# PowerSupply.net
KiCad netlist of a schematic drawn in Altium Designer
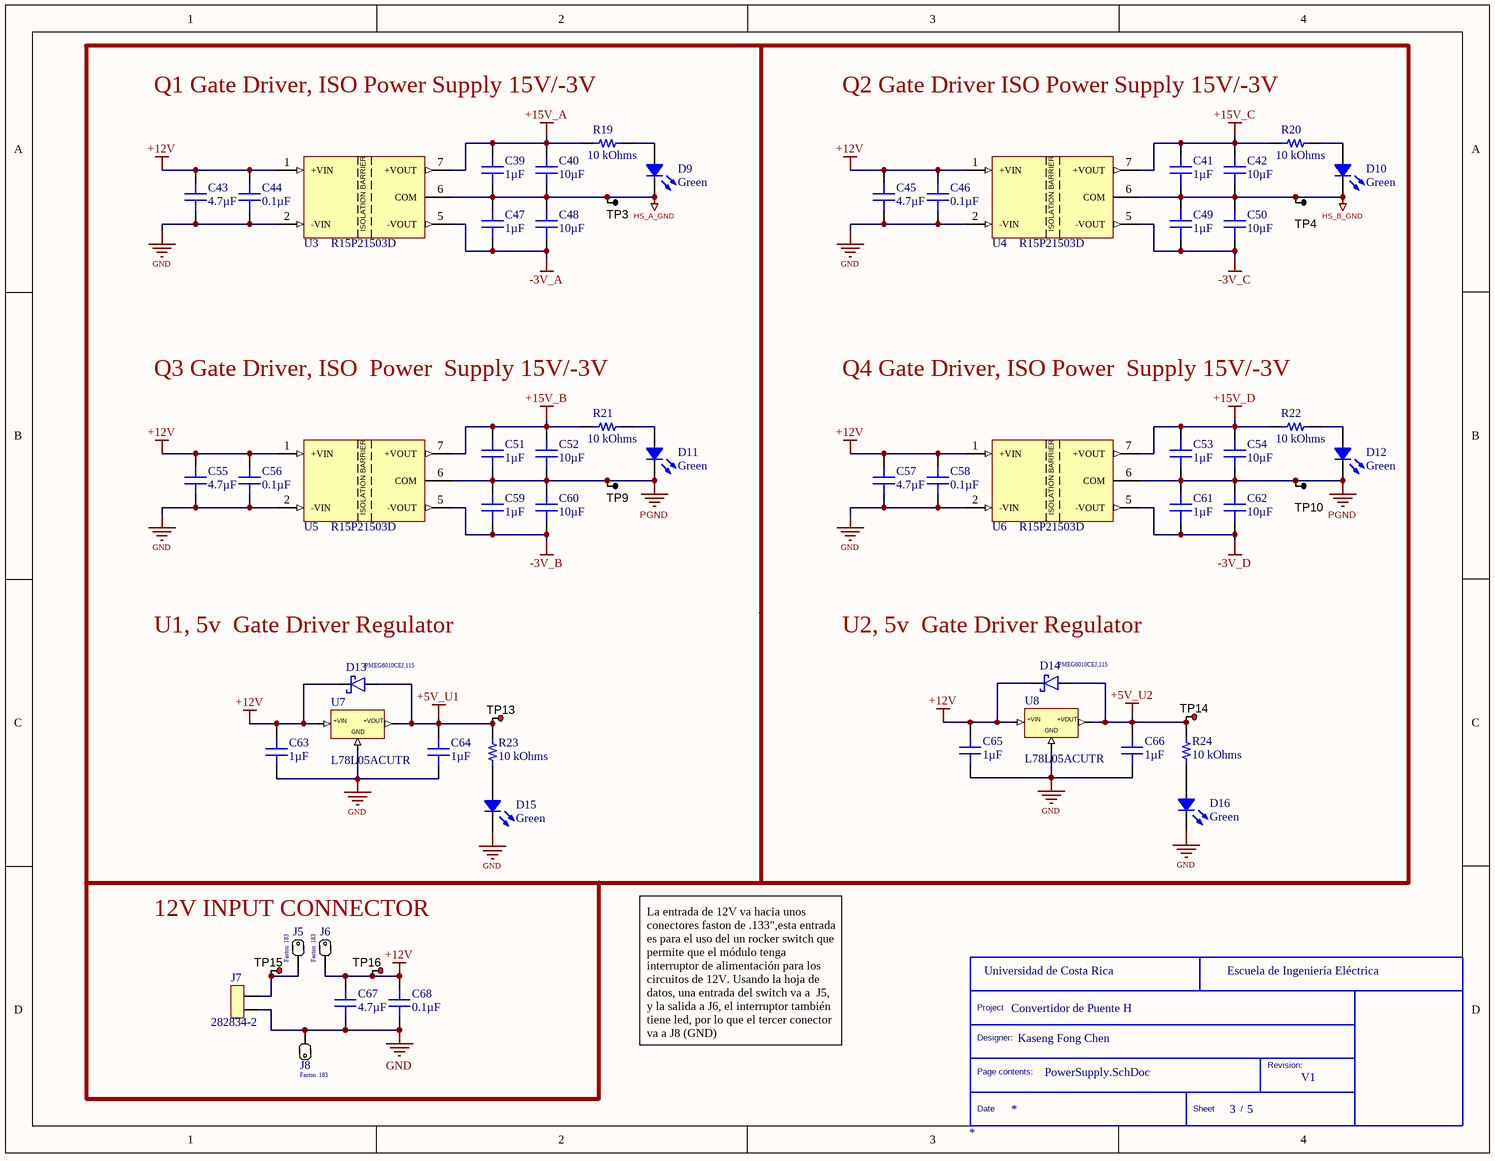
[diagram p0: PowerSupply.SchDoc]

(export (version "E")
  (design (tool "Eeschema 10.0.6"))
  (components
    (comp (ref "C39")
      (value "1µF")
      (footprint "CAP 0603_1608")
      (description "CAP CER 1UF 50V X7R 0603")
      (fields (field (name "PART NUMBER") "UMK107AB7105KA-T") (field (name "MANUFACTURER") "Taiyo Yuden"))
      (libsource (lib "Celestial Altium Library - altium_library") (part "Capacitor"))
    )
    (comp (ref "C40")
      (value "10µF")
      (footprint "CAP 1206_3216 - 1.8MM")
      (description "CAP CER 10UF 25V X7R 1206")
      (fields (field (name "PART NUMBER") "TMK316AB7106KL-T") (field (name "MANUFACTURER") "Taiyo Yuden"))
      (libsource (lib "Celestial Altium Library - altium_library") (part "Capacitor"))
    )
    (comp (ref "C41")
      (value "1µF")
      (footprint "CAP 0603_1608")
      (description "CAP CER 1UF 50V X7R 0603")
      (fields (field (name "PART NUMBER") "UMK107AB7105KA-T") (field (name "MANUFACTURER") "Taiyo Yuden"))
      (libsource (lib "Celestial Altium Library - altium_library") (part "Capacitor"))
    )
    (comp (ref "C42")
      (value "10µF")
      (footprint "CAP 1206_3216 - 1.8MM")
      (description "CAP CER 10UF 25V X7R 1206")
      (fields (field (name "PART NUMBER") "TMK316AB7106KL-T") (field (name "MANUFACTURER") "Taiyo Yuden"))
      (libsource (lib "Celestial Altium Library - altium_library") (part "Capacitor"))
    )
    (comp (ref "C43")
      (value "4.7µF")
      (footprint "CAP 1206_3216 - 1.8MM")
      (description "CAP CER 4.7UF 50V X7R 1206")
      (fields (field (name "PART NUMBER") "UMK316AB7475KL-T") (field (name "MANUFACTURER") "Taiyo Yuden"))
      (libsource (lib "Celestial Altium Library - altium_library") (part "Capacitor"))
    )
    (comp (ref "C44")
      (value "0.1µF")
      (footprint "CAP 0603_1608")
      (description "CAP CER 0.1UF 50V X7R 0603")
      (fields (field (name "PART NUMBER") "C0603C104M5RACTU") (field (name "MANUFACTURER") "KEMET"))
      (libsource (lib "Celestial Altium Library - altium_library") (part "Capacitor"))
    )
    (comp (ref "C45")
      (value "4.7µF")
      (footprint "CAP 1206_3216 - 1.8MM")
      (description "CAP CER 4.7UF 50V X7R 1206")
      (fields (field (name "PART NUMBER") "UMK316AB7475KL-T") (field (name "MANUFACTURER") "Taiyo Yuden"))
      (libsource (lib "Celestial Altium Library - altium_library") (part "Capacitor"))
    )
    (comp (ref "C46")
      (value "0.1µF")
      (footprint "CAP 0603_1608")
      (description "CAP CER 0.1UF 50V X7R 0603")
      (fields (field (name "PART NUMBER") "C0603C104M5RACTU") (field (name "MANUFACTURER") "KEMET"))
      (libsource (lib "Celestial Altium Library - altium_library") (part "Capacitor"))
    )
    (comp (ref "C47")
      (value "1µF")
      (footprint "CAP 0603_1608")
      (description "CAP CER 1UF 50V X7R 0603")
      (fields (field (name "PART NUMBER") "UMK107AB7105KA-T") (field (name "MANUFACTURER") "Taiyo Yuden"))
      (libsource (lib "Celestial Altium Library - altium_library") (part "Capacitor"))
    )
    (comp (ref "C48")
      (value "10µF")
      (footprint "CAP 1206_3216 - 1.8MM")
      (description "CAP CER 10UF 25V X7R 1206")
      (fields (field (name "PART NUMBER") "TMK316AB7106KL-T") (field (name "MANUFACTURER") "Taiyo Yuden"))
      (libsource (lib "Celestial Altium Library - altium_library") (part "Capacitor"))
    )
    (comp (ref "C49")
      (value "1µF")
      (footprint "CAP 0603_1608")
      (description "CAP CER 1UF 50V X7R 0603")
      (fields (field (name "PART NUMBER") "UMK107AB7105KA-T") (field (name "MANUFACTURER") "Taiyo Yuden"))
      (libsource (lib "Celestial Altium Library - altium_library") (part "Capacitor"))
    )
    (comp (ref "C50")
      (value "10µF")
      (footprint "CAP 1206_3216 - 1.8MM")
      (description "CAP CER 10UF 25V X7R 1206")
      (fields (field (name "PART NUMBER") "TMK316AB7106KL-T") (field (name "MANUFACTURER") "Taiyo Yuden"))
      (libsource (lib "Celestial Altium Library - altium_library") (part "Capacitor"))
    )
    (comp (ref "C51")
      (value "1µF")
      (footprint "CAP 0603_1608")
      (description "CAP CER 1UF 50V X7R 0603")
      (fields (field (name "PART NUMBER") "UMK107AB7105KA-T") (field (name "MANUFACTURER") "Taiyo Yuden"))
      (libsource (lib "Celestial Altium Library - altium_library") (part "Capacitor"))
    )
    (comp (ref "C52")
      (value "10µF")
      (footprint "CAP 1206_3216 - 1.8MM")
      (description "CAP CER 10UF 25V X7R 1206")
      (fields (field (name "PART NUMBER") "TMK316AB7106KL-T") (field (name "MANUFACTURER") "Taiyo Yuden"))
      (libsource (lib "Celestial Altium Library - altium_library") (part "Capacitor"))
    )
    (comp (ref "C53")
      (value "1µF")
      (footprint "CAP 0603_1608")
      (description "CAP CER 1UF 50V X7R 0603")
      (fields (field (name "PART NUMBER") "UMK107AB7105KA-T") (field (name "MANUFACTURER") "Taiyo Yuden"))
      (libsource (lib "Celestial Altium Library - altium_library") (part "Capacitor"))
    )
    (comp (ref "C54")
      (value "10µF")
      (footprint "CAP 1206_3216 - 1.8MM")
      (description "CAP CER 10UF 25V X7R 1206")
      (fields (field (name "PART NUMBER") "TMK316AB7106KL-T") (field (name "MANUFACTURER") "Taiyo Yuden"))
      (libsource (lib "Celestial Altium Library - altium_library") (part "Capacitor"))
    )
    (comp (ref "C55")
      (value "4.7µF")
      (footprint "CAP 1206_3216 - 1.8MM")
      (description "CAP CER 4.7UF 50V X7R 1206")
      (fields (field (name "PART NUMBER") "UMK316AB7475KL-T") (field (name "MANUFACTURER") "Taiyo Yuden"))
      (libsource (lib "Celestial Altium Library - altium_library") (part "Capacitor"))
    )
    (comp (ref "C56")
      (value "0.1µF")
      (footprint "CAP 0603_1608")
      (description "CAP CER 0.1UF 50V X7R 0603")
      (fields (field (name "PART NUMBER") "C0603C104M5RACTU") (field (name "MANUFACTURER") "KEMET"))
      (libsource (lib "Celestial Altium Library - altium_library") (part "Capacitor"))
    )
    (comp (ref "C57")
      (value "4.7µF")
      (footprint "CAP 1206_3216 - 1.8MM")
      (description "CAP CER 4.7UF 50V X7R 1206")
      (fields (field (name "PART NUMBER") "UMK316AB7475KL-T") (field (name "MANUFACTURER") "Taiyo Yuden"))
      (libsource (lib "Celestial Altium Library - altium_library") (part "Capacitor"))
    )
    (comp (ref "C58")
      (value "0.1µF")
      (footprint "CAP 0603_1608")
      (description "CAP CER 0.1UF 50V X7R 0603")
      (fields (field (name "PART NUMBER") "C0603C104M5RACTU") (field (name "MANUFACTURER") "KEMET"))
      (libsource (lib "Celestial Altium Library - altium_library") (part "Capacitor"))
    )
    (comp (ref "C59")
      (value "1µF")
      (footprint "CAP 0603_1608")
      (description "CAP CER 1UF 50V X7R 0603")
      (fields (field (name "PART NUMBER") "UMK107AB7105KA-T") (field (name "MANUFACTURER") "Taiyo Yuden"))
      (libsource (lib "Celestial Altium Library - altium_library") (part "Capacitor"))
    )
    (comp (ref "C60")
      (value "10µF")
      (footprint "CAP 1206_3216 - 1.8MM")
      (description "CAP CER 10UF 25V X7R 1206")
      (fields (field (name "PART NUMBER") "TMK316AB7106KL-T") (field (name "MANUFACTURER") "Taiyo Yuden"))
      (libsource (lib "Celestial Altium Library - altium_library") (part "Capacitor"))
    )
    (comp (ref "C61")
      (value "1µF")
      (footprint "CAP 0603_1608")
      (description "CAP CER 1UF 50V X7R 0603")
      (fields (field (name "PART NUMBER") "UMK107AB7105KA-T") (field (name "MANUFACTURER") "Taiyo Yuden"))
      (libsource (lib "Celestial Altium Library - altium_library") (part "Capacitor"))
    )
    (comp (ref "C62")
      (value "10µF")
      (footprint "CAP 1206_3216 - 1.8MM")
      (description "CAP CER 10UF 25V X7R 1206")
      (fields (field (name "PART NUMBER") "TMK316AB7106KL-T") (field (name "MANUFACTURER") "Taiyo Yuden"))
      (libsource (lib "Celestial Altium Library - altium_library") (part "Capacitor"))
    )
    (comp (ref "C63")
      (value "1µF")
      (footprint "CAP 0603_1608")
      (description "CAP CER 1UF 25V X7R 0603")
      (fields (field (name "PART NUMBER") "TMK107B7105KA-T") (field (name "MANUFACTURER") "Taiyo Yuden"))
      (libsource (lib "Celestial Altium Library - altium_library") (part "Capacitor"))
    )
    (comp (ref "C64")
      (value "1µF")
      (footprint "CAP 0603_1608")
      (description "CAP CER 1UF 16V X7R 0603")
      (fields (field (name "PART NUMBER") "CC0603KRX7R7BB105") (field (name "MANUFACTURER") "Yageo"))
      (libsource (lib "Celestial Altium Library - altium_library") (part "Capacitor"))
    )
    (comp (ref "C65")
      (value "1µF")
      (footprint "CAP 0603_1608")
      (description "CAP CER 1UF 25V X7R 0603")
      (fields (field (name "PART NUMBER") "TMK107B7105KA-T") (field (name "MANUFACTURER") "Taiyo Yuden"))
      (libsource (lib "Celestial Altium Library - altium_library") (part "Capacitor"))
    )
    (comp (ref "C66")
      (value "1µF")
      (footprint "CAP 0603_1608")
      (description "CAP CER 1UF 16V X7R 0603")
      (fields (field (name "PART NUMBER") "CC0603KRX7R7BB105") (field (name "MANUFACTURER") "Yageo"))
      (libsource (lib "Celestial Altium Library - altium_library") (part "Capacitor"))
    )
    (comp (ref "C67")
      (value "4.7µF")
      (footprint "CAP 1206_3216 - 1.8MM")
      (description "CAP CER 4.7UF 50V X7R 1206")
      (fields (field (name "PART NUMBER") "UMK316AB7475KL-T") (field (name "MANUFACTURER") "Taiyo Yuden"))
      (libsource (lib "Celestial Altium Library - altium_library") (part "Capacitor"))
    )
    (comp (ref "C68")
      (value "0.1µF")
      (footprint "CAP 0603_1608")
      (description "CAP CER 0.1UF 50V X7R 0603")
      (fields (field (name "PART NUMBER") "C0603C104M5RACTU") (field (name "MANUFACTURER") "KEMET"))
      (libsource (lib "Celestial Altium Library - altium_library") (part "Capacitor"))
    )
    (comp (ref "D9")
      (value "Green")
      (footprint "LED 0603_1608 GREEN")
      (description "LED GREEN CLEAR 0603 SMD")
      (fields (field (name "PART NUMBER") "150060GS75000") (field (name "MANUFACTURER") "Würth Elektronik"))
      (libsource (lib "Celestial Altium Library - altium_library") (part "LED"))
    )
    (comp (ref "D10")
      (value "Green")
      (footprint "LED 0603_1608 GREEN")
      (description "LED GREEN CLEAR 0603 SMD")
      (fields (field (name "PART NUMBER") "150060GS75000") (field (name "MANUFACTURER") "Würth Elektronik"))
      (libsource (lib "Celestial Altium Library - altium_library") (part "LED"))
    )
    (comp (ref "D11")
      (value "Green")
      (footprint "LED 0603_1608 GREEN")
      (description "LED GREEN CLEAR 0603 SMD")
      (fields (field (name "PART NUMBER") "150060GS75000") (field (name "MANUFACTURER") "Würth Elektronik"))
      (libsource (lib "Celestial Altium Library - altium_library") (part "LED"))
    )
    (comp (ref "D12")
      (value "Green")
      (footprint "LED 0603_1608 GREEN")
      (description "LED GREEN CLEAR 0603 SMD")
      (fields (field (name "PART NUMBER") "150060GS75000") (field (name "MANUFACTURER") "Würth Elektronik"))
      (libsource (lib "Celestial Altium Library - altium_library") (part "LED"))
    )
    (comp (ref "D13")
      (value "PMEG6010CEJ,115")
      (footprint "SOD-323F")
      (description "PMEG6010CEH; PMEG6010CEJ - 1 A very low VF MEGA Schottky barrier rectifiers")
      (fields (field (name "MANUFACTURER") "Nexperia"))
      (libsource (lib "KasengLIb") (part "PMEG6010CEJ,115"))
    )
    (comp (ref "D14")
      (value "PMEG6010CEJ,115")
      (footprint "SOD-323F")
      (description "PMEG6010CEH; PMEG6010CEJ - 1 A very low VF MEGA Schottky barrier rectifiers")
      (fields (field (name "MANUFACTURER") "Nexperia"))
      (libsource (lib "KasengLIb") (part "PMEG6010CEJ,115"))
    )
    (comp (ref "D15")
      (value "Green")
      (footprint "LED 0603_1608 GREEN")
      (description "LED GREEN CLEAR 0603 SMD")
      (fields (field (name "PART NUMBER") "150060GS75000") (field (name "MANUFACTURER") "Würth Elektronik"))
      (libsource (lib "Celestial Altium Library - altium_library") (part "LED"))
    )
    (comp (ref "D16")
      (value "Green")
      (footprint "LED 0603_1608 GREEN")
      (description "LED GREEN CLEAR 0603 SMD")
      (fields (field (name "PART NUMBER") "150060GS75000") (field (name "MANUFACTURER") "Würth Elektronik"))
      (libsource (lib "Celestial Altium Library - altium_library") (part "LED"))
    )
    (comp (ref "J5")
      (value "Faston .183")
      (footprint "TE_1217133-1")
      (description "FASTON 187 PCB TAB TPBR")
      (fields (field (name "MP") "1217133-1") (field (name "MF") "TE Connectivity"))
      (libsource (lib "1217133-1") (part "1217133-1"))
    )
    (comp (ref "J6")
      (value "Faston .183")
      (footprint "TE_1217133-1")
      (description "FASTON 187 PCB TAB TPBR")
      (fields (field (name "MP") "1217133-1") (field (name "MF") "TE Connectivity"))
      (libsource (lib "1217133-1") (part "1217133-1"))
    )
    (comp (ref "J7")
      (value "282834-2")
      (footprint "TE 282834-2")
      (description "TE CONNECTIVITY / BUCHANAN - 282834-2 - TERMINAL BLOCK, WIRE TO BRD, 2POS, 16AWG")
      (fields (field (name "MANUFACTURER") "TE Connectivity") (field (name "VOLTAGE") "150V"))
      (libsource (lib "kasengLib") (part "282834-2"))
    )
    (comp (ref "J8")
      (value "Faston .183")
      (footprint "TE_1217133-1")
      (description "FASTON 187 PCB TAB TPBR")
      (fields (field (name "MP") "1217133-1") (field (name "MF") "TE Connectivity"))
      (libsource (lib "1217133-1") (part "1217133-1"))
    )
    (comp (ref "R19")
      (value "10 kOhms")
      (footprint "RES 0603_1608")
      (description "RES SMD 10K OHM 1% 1/10W 0603")
      (fields (field (name "PART NUMBER") "RC0603FR-0710KL") (field (name "MANUFACTURER") "Yageo"))
      (libsource (lib "Celestial Altium Library - altium_library") (part "Resistor"))
    )
    (comp (ref "R20")
      (value "10 kOhms")
      (footprint "RES 0603_1608")
      (description "RES SMD 10K OHM 1% 1/10W 0603")
      (fields (field (name "PART NUMBER") "RC0603FR-0710KL") (field (name "MANUFACTURER") "Yageo"))
      (libsource (lib "Celestial Altium Library - altium_library") (part "Resistor"))
    )
    (comp (ref "R21")
      (value "10 kOhms")
      (footprint "RES 0603_1608")
      (description "RES SMD 10K OHM 1% 1/10W 0603")
      (fields (field (name "PART NUMBER") "RC0603FR-0710KL") (field (name "MANUFACTURER") "Yageo"))
      (libsource (lib "Celestial Altium Library - altium_library") (part "Resistor"))
    )
    (comp (ref "R22")
      (value "10 kOhms")
      (footprint "RES 0603_1608")
      (description "RES SMD 10K OHM 1% 1/10W 0603")
      (fields (field (name "PART NUMBER") "RC0603FR-0710KL") (field (name "MANUFACTURER") "Yageo"))
      (libsource (lib "Celestial Altium Library - altium_library") (part "Resistor"))
    )
    (comp (ref "R23")
      (value "10 kOhms")
      (footprint "RES 0603_1608")
      (description "RES SMD 10K OHM 1% 1/10W 0603")
      (fields (field (name "PART NUMBER") "RC0603FR-0710KL") (field (name "MANUFACTURER") "Yageo"))
      (libsource (lib "Celestial Altium Library - altium_library") (part "Resistor"))
    )
    (comp (ref "R24")
      (value "10 kOhms")
      (footprint "RES 0603_1608")
      (description "RES SMD 10K OHM 1% 1/10W 0603")
      (fields (field (name "PART NUMBER") "RC0603FR-0710KL") (field (name "MANUFACTURER") "Yageo"))
      (libsource (lib "Celestial Altium Library - altium_library") (part "Resistor"))
    )
    (comp (ref "TP3")
      (value "5011")
      (footprint "Keystone5011")
      (description "Test Point, Multipurpose, Black, TH")
      (fields (field (name "MANUFACTURER") "Keystone") (field (name "PUBLISHER") "Texas Instruments"))
      (libsource (lib "kasengLib") (part "5011"))
    )
    (comp (ref "TP4")
      (value "5011")
      (footprint "Keystone5011")
      (description "Test Point, Multipurpose, Black, TH")
      (fields (field (name "MANUFACTURER") "Keystone") (field (name "PUBLISHER") "Texas Instruments"))
      (libsource (lib "kasengLib") (part "5011"))
    )
    (comp (ref "TP9")
      (value "5011")
      (footprint "Keystone5011")
      (description "Test Point, Multipurpose, Black, TH")
      (fields (field (name "MANUFACTURER") "Keystone") (field (name "PUBLISHER") "Texas Instruments"))
      (libsource (lib "kasengLib") (part "5011"))
    )
    (comp (ref "TP10")
      (value "5011")
      (footprint "Keystone5011")
      (description "Test Point, Multipurpose, Black, TH")
      (fields (field (name "MANUFACTURER") "Keystone") (field (name "PUBLISHER") "Texas Instruments"))
      (libsource (lib "kasengLib") (part "5011"))
    )
    (comp (ref "TP13")
      (value "5010")
      (footprint "Keystone5010")
      (description "Test Point, Multipurpose, Red, TH")
      (fields (field (name "MANUFACTURER") "Keystone") (field (name "PUBLISHER") "Texas Instruments"))
      (libsource (lib "kasengLib") (part "5010"))
    )
    (comp (ref "TP14")
      (value "5010")
      (footprint "Keystone5010")
      (description "Test Point, Multipurpose, Red, TH")
      (fields (field (name "MANUFACTURER") "Keystone") (field (name "PUBLISHER") "Texas Instruments"))
      (libsource (lib "kasengLib") (part "5010"))
    )
    (comp (ref "TP15")
      (value "5010")
      (footprint "Keystone5010")
      (description "Test Point, Multipurpose, Red, TH")
      (fields (field (name "MANUFACTURER") "Keystone") (field (name "PUBLISHER") "Texas Instruments"))
      (libsource (lib "kasengLib") (part "5010"))
    )
    (comp (ref "TP16")
      (value "5010")
      (footprint "Keystone5010")
      (description "Test Point, Multipurpose, Red, TH")
      (fields (field (name "MANUFACTURER") "Keystone") (field (name "PUBLISHER") "Texas Instruments"))
      (libsource (lib "kasengLib") (part "5010"))
    )
    (comp (ref "U3")
      (value "R15P21503D")
      (footprint "CONV_R15P21503D")
      (description "2W DC/DC-Converter 'ECONOLINE' SIP7 6.4kV unreg; V. In: 15; V. Out: +15/-03; mA. Out: +93/-185")
      (fields (field (name "MANUFACTURER") "Recom"))
      (libsource (lib "KasengLIb") (part "R15P21503D"))
    )
    (comp (ref "U4")
      (value "R15P21503D")
      (footprint "CONV_R15P21503D")
      (description "2W DC/DC-Converter 'ECONOLINE' SIP7 6.4kV unreg; V. In: 15; V. Out: +15/-03; mA. Out: +93/-185")
      (fields (field (name "MANUFACTURER") "Recom"))
      (libsource (lib "KasengLIb") (part "R15P21503D"))
    )
    (comp (ref "U5")
      (value "R15P21503D")
      (footprint "CONV_R15P21503D")
      (description "2W DC/DC-Converter 'ECONOLINE' SIP7 6.4kV unreg; V. In: 15; V. Out: +15/-03; mA. Out: +93/-185")
      (fields (field (name "MANUFACTURER") "Recom"))
      (libsource (lib "KasengLIb") (part "R15P21503D"))
    )
    (comp (ref "U6")
      (value "R15P21503D")
      (footprint "CONV_R15P21503D")
      (description "2W DC/DC-Converter 'ECONOLINE' SIP7 6.4kV unreg; V. In: 15; V. Out: +15/-03; mA. Out: +93/-185")
      (fields (field (name "MANUFACTURER") "Recom"))
      (libsource (lib "KasengLIb") (part "R15P21503D"))
    )
    (comp (ref "U7")
      (value "L78L05ACUTR")
      (footprint "VREG_L78L12ABUTR")
      (description "Voltage regulator; linear, fixed; 5V; 0.1A; SOT89; SMD; 0÷125°C")
      (fields (field (name "MANUFACTURER") "STMicroelectronics"))
      (libsource (lib "KasengLIb") (part "L78L05ACUTR"))
    )
    (comp (ref "U8")
      (value "L78L05ACUTR")
      (footprint "VREG_L78L12ABUTR")
      (description "Voltage regulator; linear, fixed; 5V; 0.1A; SOT89; SMD; 0÷125°C")
      (fields (field (name "MANUFACTURER") "STMicroelectronics"))
      (libsource (lib "KasengLIb") (part "L78L05ACUTR"))
    )
  )
  (nets
    (net (code "1") (name "+5V_U1") (class "Default")
      (node (ref "C64") (pin "2") (pinfunction "2_2") (pintype "passive"))
      (node (ref "D13") (pin "2") (pinfunction "2_2") (pintype "passive"))
      (node (ref "R23") (pin "1") (pinfunction "1_1") (pintype "passive"))
      (node (ref "TP13") (pin "1") (pinfunction "1_1") (pintype "passive"))
      (node (ref "U7") (pin "1") (pinfunction "OUT_1") (pintype "output"))
    )
    (net (code "2") (name "+5V_U2") (class "Default")
      (node (ref "C66") (pin "2") (pinfunction "2_2") (pintype "passive"))
      (node (ref "D14") (pin "2") (pinfunction "2_2") (pintype "passive"))
      (node (ref "R24") (pin "1") (pinfunction "1_1") (pintype "passive"))
      (node (ref "TP14") (pin "1") (pinfunction "1_1") (pintype "passive"))
      (node (ref "U8") (pin "1") (pinfunction "OUT_1") (pintype "output"))
    )
    (net (code "3") (name "+12V") (class "Default")
      (node (ref "C43") (pin "2") (pinfunction "2_2") (pintype "passive"))
      (node (ref "C44") (pin "2") (pinfunction "2_2") (pintype "passive"))
      (node (ref "C45") (pin "2") (pinfunction "2_2") (pintype "passive"))
      (node (ref "C46") (pin "2") (pinfunction "2_2") (pintype "passive"))
      (node (ref "C55") (pin "2") (pinfunction "2_2") (pintype "passive"))
      (node (ref "C56") (pin "2") (pinfunction "2_2") (pintype "passive"))
      (node (ref "C57") (pin "2") (pinfunction "2_2") (pintype "passive"))
      (node (ref "C58") (pin "2") (pinfunction "2_2") (pintype "passive"))
      (node (ref "C63") (pin "2") (pinfunction "2_2") (pintype "passive"))
      (node (ref "C65") (pin "2") (pinfunction "2_2") (pintype "passive"))
      (node (ref "C67") (pin "2") (pinfunction "2_2") (pintype "passive"))
      (node (ref "C68") (pin "2") (pinfunction "2_2") (pintype "passive"))
      (node (ref "D13") (pin "1") (pinfunction "1_1") (pintype "passive"))
      (node (ref "D14") (pin "1") (pinfunction "1_1") (pintype "passive"))
      (node (ref "J6") (pin "1") (pinfunction "P1_1") (pintype "passive"))
      (node (ref "TP16") (pin "1") (pinfunction "1_1") (pintype "passive"))
      (node (ref "U3") (pin "1") (pinfunction "+VIN_1") (pintype "input"))
      (node (ref "U4") (pin "1") (pinfunction "+VIN_1") (pintype "input"))
      (node (ref "U5") (pin "1") (pinfunction "+VIN_1") (pintype "input"))
      (node (ref "U6") (pin "1") (pinfunction "+VIN_1") (pintype "input"))
      (node (ref "U7") (pin "3") (pinfunction "IN_3") (pintype "input"))
      (node (ref "U8") (pin "3") (pinfunction "IN_3") (pintype "input"))
    )
    (net (code "4") (name "+15V_A") (class "Default")
      (node (ref "C39") (pin "2") (pinfunction "2_2") (pintype "passive"))
      (node (ref "C40") (pin "2") (pinfunction "2_2") (pintype "passive"))
      (node (ref "R19") (pin "1") (pinfunction "1_1") (pintype "passive"))
      (node (ref "U3") (pin "7") (pinfunction "+VOUT_7") (pintype "output"))
    )
    (net (code "5") (name "+15V_B") (class "Default")
      (node (ref "C51") (pin "2") (pinfunction "2_2") (pintype "passive"))
      (node (ref "C52") (pin "2") (pinfunction "2_2") (pintype "passive"))
      (node (ref "R21") (pin "1") (pinfunction "1_1") (pintype "passive"))
      (node (ref "U5") (pin "7") (pinfunction "+VOUT_7") (pintype "output"))
    )
    (net (code "6") (name "+15V_C") (class "Default")
      (node (ref "C41") (pin "2") (pinfunction "2_2") (pintype "passive"))
      (node (ref "C42") (pin "2") (pinfunction "2_2") (pintype "passive"))
      (node (ref "R20") (pin "1") (pinfunction "1_1") (pintype "passive"))
      (node (ref "U4") (pin "7") (pinfunction "+VOUT_7") (pintype "output"))
    )
    (net (code "7") (name "+15V_D") (class "Default")
      (node (ref "C53") (pin "2") (pinfunction "2_2") (pintype "passive"))
      (node (ref "C54") (pin "2") (pinfunction "2_2") (pintype "passive"))
      (node (ref "R22") (pin "1") (pinfunction "1_1") (pintype "passive"))
      (node (ref "U6") (pin "7") (pinfunction "+VOUT_7") (pintype "output"))
    )
    (net (code "8") (name "-3V_A") (class "Default")
      (node (ref "C47") (pin "1") (pinfunction "1_1") (pintype "passive"))
      (node (ref "C48") (pin "1") (pinfunction "1_1") (pintype "passive"))
      (node (ref "U3") (pin "5") (pinfunction "-VOUT_5") (pintype "output"))
    )
    (net (code "9") (name "-3V_B") (class "Default")
      (node (ref "C59") (pin "1") (pinfunction "1_1") (pintype "passive"))
      (node (ref "C60") (pin "1") (pinfunction "1_1") (pintype "passive"))
      (node (ref "U5") (pin "5") (pinfunction "-VOUT_5") (pintype "output"))
    )
    (net (code "10") (name "-3V_C") (class "Default")
      (node (ref "C49") (pin "1") (pinfunction "1_1") (pintype "passive"))
      (node (ref "C50") (pin "1") (pinfunction "1_1") (pintype "passive"))
      (node (ref "U4") (pin "5") (pinfunction "-VOUT_5") (pintype "output"))
    )
    (net (code "11") (name "-3V_D") (class "Default")
      (node (ref "C61") (pin "1") (pinfunction "1_1") (pintype "passive"))
      (node (ref "C62") (pin "1") (pinfunction "1_1") (pintype "passive"))
      (node (ref "U6") (pin "5") (pinfunction "-VOUT_5") (pintype "output"))
    )
    (net (code "12") (name "GND") (class "Default")
      (node (ref "C43") (pin "1") (pinfunction "1_1") (pintype "passive"))
      (node (ref "C44") (pin "1") (pinfunction "1_1") (pintype "passive"))
      (node (ref "C45") (pin "1") (pinfunction "1_1") (pintype "passive"))
      (node (ref "C46") (pin "1") (pinfunction "1_1") (pintype "passive"))
      (node (ref "C55") (pin "1") (pinfunction "1_1") (pintype "passive"))
      (node (ref "C56") (pin "1") (pinfunction "1_1") (pintype "passive"))
      (node (ref "C57") (pin "1") (pinfunction "1_1") (pintype "passive"))
      (node (ref "C58") (pin "1") (pinfunction "1_1") (pintype "passive"))
      (node (ref "C63") (pin "1") (pinfunction "1_1") (pintype "passive"))
      (node (ref "C64") (pin "1") (pinfunction "1_1") (pintype "passive"))
      (node (ref "C65") (pin "1") (pinfunction "1_1") (pintype "passive"))
      (node (ref "C66") (pin "1") (pinfunction "1_1") (pintype "passive"))
      (node (ref "C67") (pin "1") (pinfunction "1_1") (pintype "passive"))
      (node (ref "C68") (pin "1") (pinfunction "1_1") (pintype "passive"))
      (node (ref "D15") (pin "2") (pinfunction "2_2") (pintype "passive"))
      (node (ref "D16") (pin "2") (pinfunction "2_2") (pintype "passive"))
      (node (ref "J7") (pin "2") (pinfunction "2_2") (pintype "passive"))
      (node (ref "J8") (pin "1") (pinfunction "P1_1") (pintype "passive"))
      (node (ref "U3") (pin "2") (pinfunction "-VIN_2") (pintype "input"))
      (node (ref "U4") (pin "2") (pinfunction "-VIN_2") (pintype "input"))
      (node (ref "U5") (pin "2") (pinfunction "-VIN_2") (pintype "input"))
      (node (ref "U6") (pin "2") (pinfunction "-VIN_2") (pintype "input"))
      (node (ref "U7") (pin "2") (pinfunction "GND_2") (pintype "input"))
      (node (ref "U8") (pin "2") (pinfunction "GND_2") (pintype "input"))
    )
    (net (code "13") (name "HS_A_GND") (class "Default")
      (node (ref "C39") (pin "1") (pinfunction "1_1") (pintype "passive"))
      (node (ref "C40") (pin "1") (pinfunction "1_1") (pintype "passive"))
      (node (ref "C47") (pin "2") (pinfunction "2_2") (pintype "passive"))
      (node (ref "C48") (pin "2") (pinfunction "2_2") (pintype "passive"))
      (node (ref "D9") (pin "2") (pinfunction "2_2") (pintype "passive"))
      (node (ref "TP3") (pin "1") (pinfunction "1_1") (pintype "passive"))
      (node (ref "U3") (pin "6") (pinfunction "COM_6") (pintype "power_in"))
    )
    (net (code "14") (name "HS_B_GND") (class "Default")
      (node (ref "C41") (pin "1") (pinfunction "1_1") (pintype "passive"))
      (node (ref "C42") (pin "1") (pinfunction "1_1") (pintype "passive"))
      (node (ref "C49") (pin "2") (pinfunction "2_2") (pintype "passive"))
      (node (ref "C50") (pin "2") (pinfunction "2_2") (pintype "passive"))
      (node (ref "D10") (pin "2") (pinfunction "2_2") (pintype "passive"))
      (node (ref "TP4") (pin "1") (pinfunction "1_1") (pintype "passive"))
      (node (ref "U4") (pin "6") (pinfunction "COM_6") (pintype "power_in"))
    )
    (net (code "15") (name "Net-(D9-Pad1)") (class "Default")
      (node (ref "D9") (pin "1") (pinfunction "1_1") (pintype "passive"))
      (node (ref "R19") (pin "2") (pinfunction "2_2") (pintype "passive"))
    )
    (net (code "16") (name "Net-(D10-Pad1)") (class "Default")
      (node (ref "D10") (pin "1") (pinfunction "1_1") (pintype "passive"))
      (node (ref "R20") (pin "2") (pinfunction "2_2") (pintype "passive"))
    )
    (net (code "17") (name "Net-(D11-Pad1)") (class "Default")
      (node (ref "D11") (pin "1") (pinfunction "1_1") (pintype "passive"))
      (node (ref "R21") (pin "2") (pinfunction "2_2") (pintype "passive"))
    )
    (net (code "18") (name "Net-(D12-Pad1)") (class "Default")
      (node (ref "D12") (pin "1") (pinfunction "1_1") (pintype "passive"))
      (node (ref "R22") (pin "2") (pinfunction "2_2") (pintype "passive"))
    )
    (net (code "19") (name "Net-(D15-Pad1)") (class "Default")
      (node (ref "D15") (pin "1") (pinfunction "1_1") (pintype "passive"))
      (node (ref "R23") (pin "2") (pinfunction "2_2") (pintype "passive"))
    )
    (net (code "20") (name "Net-(D16-Pad1)") (class "Default")
      (node (ref "D16") (pin "1") (pinfunction "1_1") (pintype "passive"))
      (node (ref "R24") (pin "2") (pinfunction "2_2") (pintype "passive"))
    )
    (net (code "21") (name "Net-(J5-P1)") (class "Default")
      (node (ref "J5") (pin "1") (pinfunction "P1_1") (pintype "passive"))
      (node (ref "J7") (pin "1") (pinfunction "1_1") (pintype "passive"))
      (node (ref "TP15") (pin "1") (pinfunction "1_1") (pintype "passive"))
    )
    (net (code "22") (name "PGND") (class "Default")
      (node (ref "C51") (pin "1") (pinfunction "1_1") (pintype "passive"))
      (node (ref "C52") (pin "1") (pinfunction "1_1") (pintype "passive"))
      (node (ref "C53") (pin "1") (pinfunction "1_1") (pintype "passive"))
      (node (ref "C54") (pin "1") (pinfunction "1_1") (pintype "passive"))
      (node (ref "C59") (pin "2") (pinfunction "2_2") (pintype "passive"))
      (node (ref "C60") (pin "2") (pinfunction "2_2") (pintype "passive"))
      (node (ref "C61") (pin "2") (pinfunction "2_2") (pintype "passive"))
      (node (ref "C62") (pin "2") (pinfunction "2_2") (pintype "passive"))
      (node (ref "D11") (pin "2") (pinfunction "2_2") (pintype "passive"))
      (node (ref "D12") (pin "2") (pinfunction "2_2") (pintype "passive"))
      (node (ref "TP10") (pin "1") (pinfunction "1_1") (pintype "passive"))
      (node (ref "TP9") (pin "1") (pinfunction "1_1") (pintype "passive"))
      (node (ref "U5") (pin "6") (pinfunction "COM_6") (pintype "power_in"))
      (node (ref "U6") (pin "6") (pinfunction "COM_6") (pintype "power_in"))
    )
  )
)
